# Payload_Power_Board.net
KiCad netlist of a schematic drawn in EAGLE
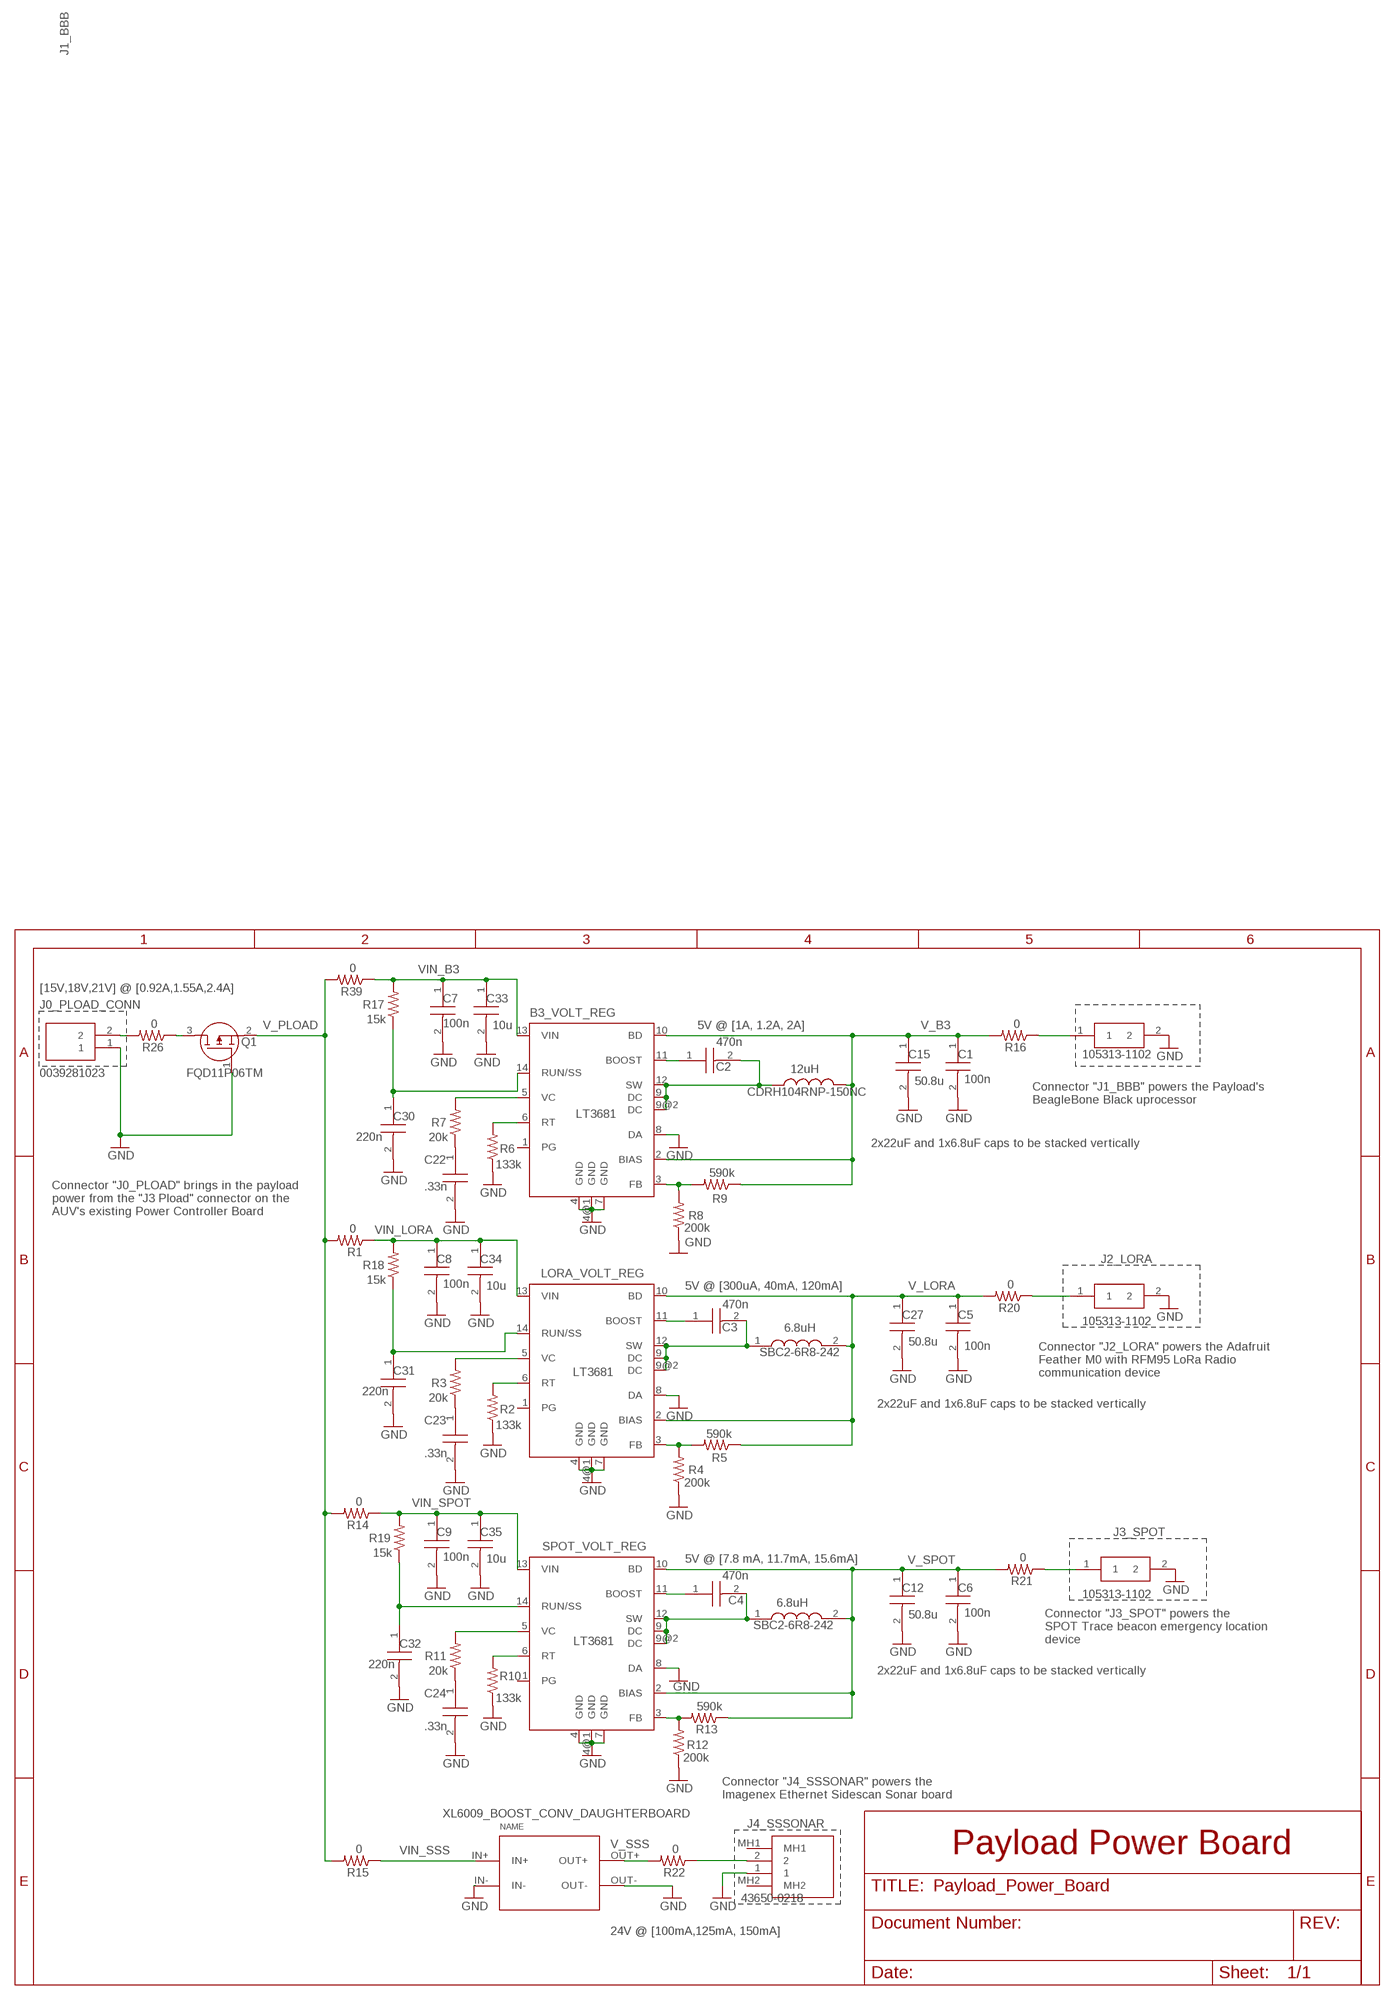
[diagram p0: schematic, sheet 1]

(export (version "E")
  (design (tool "Eeschema 10.0.6"))
  (components
    (comp (ref "B3_VOLT_REG")
      (value "LT3681")
      (footprint "eagle-import:DFN14-4X3DE")
      (fields (field (name "MPN") "LT3681EDE#PBF"))
      (libsource (lib "eagle-import") (part "LT3681"))
    )
    (comp (ref "C1")
      (value "100n")
      (footprint "eagle-import:CAPC1608X90N")
      (fields
        (field (name "MANUFACTURER_PART_NUMBER") "06033C104KAT4A")
        (field (name "MOUSER_PART_NUMBER") "581-06033C104KAT4A")
      )
      (libsource (lib "eagle-import") (part "06033C104KAT4A"))
    )
    (comp (ref "C2")
      (value "470n")
      (footprint "eagle-import:CAPC1608X90N")
      (fields
        (field (name "MANUFACTURER_PART_NUMBER") "06033C474JAT2A")
        (field (name "MOUSER_PART_NUMBER") "581-06033C474JAT2A")
      )
      (libsource (lib "eagle-import") (part "06033C474JAT2A"))
    )
    (comp (ref "C3")
      (value "470n")
      (footprint "eagle-import:CAPC1608X90N")
      (fields
        (field (name "MANUFACTURER_PART_NUMBER") "06033C474JAT2A")
        (field (name "MOUSER_PART_NUMBER") "581-06033C474JAT2A")
      )
      (libsource (lib "eagle-import") (part "06033C474JAT2A"))
    )
    (comp (ref "C4")
      (value "470n")
      (footprint "eagle-import:CAPC1608X90N")
      (fields
        (field (name "MANUFACTURER_PART_NUMBER") "06033C474JAT2A")
        (field (name "MOUSER_PART_NUMBER") "581-06033C474JAT2A")
      )
      (libsource (lib "eagle-import") (part "06033C474JAT2A"))
    )
    (comp (ref "C5")
      (value "100n")
      (footprint "eagle-import:CAPC1608X90N")
      (fields
        (field (name "MANUFACTURER_PART_NUMBER") "06033C104KAT4A")
        (field (name "MOUSER_PART_NUMBER") "581-06033C104KAT4A")
      )
      (libsource (lib "eagle-import") (part "06033C104KAT4A"))
    )
    (comp (ref "C6")
      (value "100n")
      (footprint "eagle-import:CAPC1608X90N")
      (fields
        (field (name "MANUFACTURER_PART_NUMBER") "06033C104KAT4A")
        (field (name "MOUSER_PART_NUMBER") "581-06033C104KAT4A")
      )
      (libsource (lib "eagle-import") (part "06033C104KAT4A"))
    )
    (comp (ref "C7")
      (value "100n")
      (footprint "eagle-import:CAPC1608X90N")
      (fields
        (field (name "MANUFACTURER_PART_NUMBER") "06031C104KAT2A")
        (field (name "MOUSER_PART_NUMBER") "581-06031C104KAT2A")
      )
      (libsource (lib "eagle-import") (part "06031C104KAT2A"))
    )
    (comp (ref "C8")
      (value "100n")
      (footprint "eagle-import:CAPC1608X90N")
      (fields
        (field (name "MANUFACTURER_PART_NUMBER") "06031C104KAT2A")
        (field (name "MOUSER_PART_NUMBER") "581-06031C104KAT2A")
      )
      (libsource (lib "eagle-import") (part "06031C104KAT2A"))
    )
    (comp (ref "C9")
      (value "100n")
      (footprint "eagle-import:CAPC1608X90N")
      (fields
        (field (name "MANUFACTURER_PART_NUMBER") "06031C104KAT2A")
        (field (name "MOUSER_PART_NUMBER") "581-06031C104KAT2A")
      )
      (libsource (lib "eagle-import") (part "06031C104KAT2A"))
    )
    (comp (ref "C12")
      (value "50.8u")
      (footprint "eagle-import:CAPC3225X279N")
      (fields
        (field (name "MANUFACTURER_PART_NUMBER") "12103C226KAT2A")
        (field (name "MOUSER_PART_NUMBER") "581-12103C226KAT2A")
      )
      (libsource (lib "eagle-import") (part "12103C226KAT2A"))
    )
    (comp (ref "C15")
      (value "50.8u")
      (footprint "eagle-import:CAPC3225X279N")
      (fields
        (field (name "MANUFACTURER_PART_NUMBER") "12103C226KAT2A")
        (field (name "MOUSER_PART_NUMBER") "581-12103C226KAT2A")
      )
      (libsource (lib "eagle-import") (part "12103C226KAT2A"))
    )
    (comp (ref "C22")
      (value ".33n")
      (footprint "eagle-import:CAPC2012X140N")
      (fields
        (field (name "MANUFACTURER_PART_NUMBER") "08053C334KAT2A")
        (field (name "MOUSER_PART_NUMBER") "581-08053C334KAT2A")
        (field (name "RS_PART_NUMBER") "1747387")
      )
      (libsource (lib "eagle-import") (part "08053C334KAT2A"))
    )
    (comp (ref "C23")
      (value ".33n")
      (footprint "eagle-import:CAPC2012X140N")
      (fields
        (field (name "MANUFACTURER_PART_NUMBER") "08053C334KAT2A")
        (field (name "MOUSER_PART_NUMBER") "581-08053C334KAT2A")
        (field (name "RS_PART_NUMBER") "1747387")
      )
      (libsource (lib "eagle-import") (part "08053C334KAT2A"))
    )
    (comp (ref "C24")
      (value ".33n")
      (footprint "eagle-import:CAPC2012X140N")
      (fields
        (field (name "MANUFACTURER_PART_NUMBER") "08053C334KAT2A")
        (field (name "MOUSER_PART_NUMBER") "581-08053C334KAT2A")
        (field (name "RS_PART_NUMBER") "1747387")
      )
      (libsource (lib "eagle-import") (part "08053C334KAT2A"))
    )
    (comp (ref "C27")
      (value "50.8u")
      (footprint "eagle-import:CAPC3225X279N")
      (fields
        (field (name "MANUFACTURER_PART_NUMBER") "12103C226KAT2A")
        (field (name "MOUSER_PART_NUMBER") "581-12103C226KAT2A")
      )
      (libsource (lib "eagle-import") (part "12103C226KAT2A"))
    )
    (comp (ref "C30")
      (value "220n")
      (footprint "eagle-import:CAPC2012X140N")
      (fields
        (field (name "MANUFACTURER_PART_NUMBER") "08051C224KAT2A")
        (field (name "MOUSER_PART_NUMBER") "581-08051C224KAT2A")
      )
      (libsource (lib "eagle-import") (part "08051C224KAT2A"))
    )
    (comp (ref "C31")
      (value "220n")
      (footprint "eagle-import:CAPC2012X140N")
      (fields
        (field (name "MANUFACTURER_PART_NUMBER") "08051C224KAT2A")
        (field (name "MOUSER_PART_NUMBER") "581-08051C224KAT2A")
      )
      (libsource (lib "eagle-import") (part "08051C224KAT2A"))
    )
    (comp (ref "C32")
      (value "220n")
      (footprint "eagle-import:CAPC2012X140N")
      (fields
        (field (name "MANUFACTURER_PART_NUMBER") "08051C224KAT2A")
        (field (name "MOUSER_PART_NUMBER") "581-08051C224KAT2A")
      )
      (libsource (lib "eagle-import") (part "08051C224KAT2A"))
    )
    (comp (ref "C33")
      (value "10u")
      (footprint "eagle-import:CAPC5750X279N")
      (fields
        (field (name "MANUFACTURER_PART_NUMBER") "22201C106KAT2A")
        (field (name "MOUSER_PART_NUMBER") "581-22201C106KAT2A")
      )
      (libsource (lib "eagle-import") (part "22201C106KAT2A"))
    )
    (comp (ref "C34")
      (value "10u")
      (footprint "eagle-import:CAPC5750X279N")
      (fields
        (field (name "MANUFACTURER_PART_NUMBER") "22201C106KAT2A")
        (field (name "MOUSER_PART_NUMBER") "581-22201C106KAT2A")
      )
      (libsource (lib "eagle-import") (part "22201C106KAT2A"))
    )
    (comp (ref "C35")
      (value "10u")
      (footprint "eagle-import:CAPC5750X279N")
      (fields
        (field (name "MANUFACTURER_PART_NUMBER") "22201C106KAT2A")
        (field (name "MOUSER_PART_NUMBER") "581-22201C106KAT2A")
      )
      (libsource (lib "eagle-import") (part "22201C106KAT2A"))
    )
    (comp (ref "INDUCTOR_3")
      (value "CDRH104RNP-150NC")
      (footprint "eagle-import:INDPM102100X400N")
      (fields (field (name "MOUSER_PART_NUMBER") "851-CDRH104RNP-150NC"))
      (libsource (lib "eagle-import") (part "CDRH104RNP-150NC"))
    )
    (comp (ref "J0_PLOAD_CONN")
      (value "0039281023")
      (footprint "eagle-import:SHDR2W145P0X550_1X2_960X540X13")
      (libsource (lib "eagle-import") (part "0039281023"))
    )
    (comp (ref "J1_BBB")
      (value "105313-1102")
      (footprint "eagle-import:1053131102")
      (fields (field (name "MOUSER_PART_NUMBER") "538-105313-1102") (field (name "RS_PART_NUMBER") "1623686"))
      (libsource (lib "eagle-import") (part "105313-1102"))
    )
    (comp (ref "J2_LORA")
      (value "105313-1102")
      (footprint "eagle-import:1053131102")
      (fields (field (name "MOUSER_PART_NUMBER") "538-105313-1102") (field (name "RS_PART_NUMBER") "1623686"))
      (libsource (lib "eagle-import") (part "105313-1102"))
    )
    (comp (ref "J3_SPOT")
      (value "105313-1102")
      (footprint "eagle-import:1053131102")
      (fields (field (name "MOUSER_PART_NUMBER") "538-105313-1102") (field (name "RS_PART_NUMBER") "1623686"))
      (libsource (lib "eagle-import") (part "105313-1102"))
    )
    (comp (ref "J4_SSSONAR")
      (value "43650-0218")
      (footprint "eagle-import:436500218")
      (fields (field (name "MOUSER_PART_NUMBER") "538-43650-0218") (field (name "RS_PART_NUMBER") "6704705P"))
      (libsource (lib "eagle-import") (part "43650-0218"))
    )
    (comp (ref "L4")
      (value "SBC2-6R8-242")
      (footprint "eagle-import:SBC26R8242")
      (fields (field (name "MOUSER_PART_NUMBER") "80-SBC2-6R8-242"))
      (libsource (lib "eagle-import") (part "SBC2-6R8-242"))
    )
    (comp (ref "L5")
      (value "SBC2-6R8-242")
      (footprint "eagle-import:SBC26R8242")
      (fields (field (name "MOUSER_PART_NUMBER") "80-SBC2-6R8-242"))
      (libsource (lib "eagle-import") (part "SBC2-6R8-242"))
    )
    (comp (ref "LORA_VOLT_REG")
      (value "LT3681")
      (footprint "eagle-import:DFN14-4X3DE")
      (fields (field (name "MPN") "LT3681EDE#PBF"))
      (libsource (lib "eagle-import") (part "LT3681"))
    )
    (comp (ref "Q1")
      (value "FQD11P06TM")
      (footprint "eagle-import:DPAK3-CASE-369AS")
      (fields (field (name "MOUSER_PART_NUMBER") "512-FQD11P06TM") (field (name "RS_PART_NUMBER") "6710949P"))
      (libsource (lib "eagle-import") (part "FQD11P06TM"))
    )
    (comp (ref "R1")
      (value "0")
      (footprint "eagle-import:0207_2V")
      (fields (field (name "MFR") "Yageo") (field (name "MPN") "RC0805FR-0710KL"))
      (libsource (lib "eagle-import") (part "R-US_0207/2V"))
    )
    (comp (ref "R2")
      (value "133k")
      (footprint "eagle-import:R0603")
      (libsource (lib "eagle-import") (part "R-US_R0603"))
    )
    (comp (ref "R3")
      (value "20k")
      (footprint "eagle-import:R0603")
      (libsource (lib "eagle-import") (part "R-US_R0603"))
    )
    (comp (ref "R4")
      (value "200k")
      (footprint "eagle-import:R0603")
      (libsource (lib "eagle-import") (part "R-US_R0603"))
    )
    (comp (ref "R5")
      (value "590k")
      (footprint "eagle-import:R0603")
      (libsource (lib "eagle-import") (part "R-US_R0603"))
    )
    (comp (ref "R6")
      (value "133k")
      (footprint "eagle-import:R0603")
      (libsource (lib "eagle-import") (part "R-US_R0603"))
    )
    (comp (ref "R7")
      (value "20k")
      (footprint "eagle-import:R0603")
      (libsource (lib "eagle-import") (part "R-US_R0603"))
    )
    (comp (ref "R8")
      (value "200k")
      (footprint "eagle-import:R0603")
      (libsource (lib "eagle-import") (part "R-US_R0603"))
    )
    (comp (ref "R9")
      (value "590k")
      (footprint "eagle-import:R0603")
      (libsource (lib "eagle-import") (part "R-US_R0603"))
    )
    (comp (ref "R10")
      (value "133k")
      (footprint "eagle-import:R0603")
      (libsource (lib "eagle-import") (part "R-US_R0603"))
    )
    (comp (ref "R11")
      (value "20k")
      (footprint "eagle-import:R0603")
      (libsource (lib "eagle-import") (part "R-US_R0603"))
    )
    (comp (ref "R12")
      (value "200k")
      (footprint "eagle-import:R0603")
      (libsource (lib "eagle-import") (part "R-US_R0603"))
    )
    (comp (ref "R13")
      (value "590k")
      (footprint "eagle-import:R0603")
      (libsource (lib "eagle-import") (part "R-US_R0603"))
    )
    (comp (ref "R14")
      (value "0")
      (footprint "eagle-import:0207_2V")
      (fields (field (name "MFR") "Yageo") (field (name "MPN") "RC0805FR-0710KL"))
      (libsource (lib "eagle-import") (part "R-US_0207/2V"))
    )
    (comp (ref "R15")
      (value "0")
      (footprint "eagle-import:0207_2V")
      (fields (field (name "MFR") "Yageo") (field (name "MPN") "RC0805FR-0710KL"))
      (libsource (lib "eagle-import") (part "R-US_0207/2V"))
    )
    (comp (ref "R16")
      (value "0")
      (footprint "eagle-import:0207_2V")
      (fields (field (name "MFR") "Yageo") (field (name "MPN") "RC0805FR-0710KL"))
      (libsource (lib "eagle-import") (part "R-US_0207/2V"))
    )
    (comp (ref "R17")
      (value "15k")
      (footprint "eagle-import:R0603")
      (libsource (lib "eagle-import") (part "R-US_R0603"))
    )
    (comp (ref "R18")
      (value "15k")
      (footprint "eagle-import:R0603")
      (libsource (lib "eagle-import") (part "R-US_R0603"))
    )
    (comp (ref "R19")
      (value "15k")
      (footprint "eagle-import:R0603")
      (libsource (lib "eagle-import") (part "R-US_R0603"))
    )
    (comp (ref "R20")
      (value "0")
      (footprint "eagle-import:0207_2V")
      (fields (field (name "MFR") "Yageo") (field (name "MPN") "RC0805FR-0710KL"))
      (libsource (lib "eagle-import") (part "R-US_0207/2V"))
    )
    (comp (ref "R21")
      (value "0")
      (footprint "eagle-import:0207_2V")
      (fields (field (name "MFR") "Yageo") (field (name "MPN") "RC0805FR-0710KL"))
      (libsource (lib "eagle-import") (part "R-US_0207/2V"))
    )
    (comp (ref "R22")
      (value "0")
      (footprint "eagle-import:0207_2V")
      (fields (field (name "MFR") "Yageo") (field (name "MPN") "RC0805FR-0710KL"))
      (libsource (lib "eagle-import") (part "R-US_0207/2V"))
    )
    (comp (ref "R26")
      (value "0")
      (footprint "eagle-import:0207_2V")
      (fields (field (name "MFR") "Yageo") (field (name "MPN") "RC0805FR-0710KL"))
      (libsource (lib "eagle-import") (part "R-US_0207/2V"))
    )
    (comp (ref "R39")
      (value "0")
      (footprint "eagle-import:0207_2V")
      (fields (field (name "MFR") "Yageo") (field (name "MPN") "RC0805FR-0710KL"))
      (libsource (lib "eagle-import") (part "R-US_0207/2V"))
    )
    (comp (ref "SPOT_VOLT_REG")
      (value "LT3681")
      (footprint "eagle-import:DFN14-4X3DE")
      (fields (field (name "MPN") "LT3681EDE#PBF"))
      (libsource (lib "eagle-import") (part "LT3681"))
    )
    (comp (ref "XL6009_BOOST_CONV_DAUGHTERBOARD")
      (value "XL6009")
      (footprint "eagle-import:CP8-ADJ")
      (libsource (lib "eagle-import") (part "CP8-ADJ"))
    )
  )
  (nets
    (net (code "1") (name "/VIN_B3") (class "Default")
      (node (ref "B3_VOLT_REG") (pin "13") (pinfunction "VIN_13") (pintype "input"))
      (node (ref "C33") (pin "1") (pinfunction "1_1") (pintype "bidirectional"))
      (node (ref "C7") (pin "1") (pinfunction "1_1") (pintype "bidirectional"))
      (node (ref "R17") (pin "2") (pinfunction "2_2") (pintype "passive"))
      (node (ref "R39") (pin "1") (pinfunction "1_1") (pintype "passive"))
    )
    (net (code "2") (name "/VIN_LORA") (class "Default")
      (node (ref "C34") (pin "1") (pinfunction "1_1") (pintype "bidirectional"))
      (node (ref "C8") (pin "1") (pinfunction "1_1") (pintype "bidirectional"))
      (node (ref "LORA_VOLT_REG") (pin "13") (pinfunction "VIN_13") (pintype "input"))
      (node (ref "R1") (pin "1") (pinfunction "1_1") (pintype "passive"))
      (node (ref "R18") (pin "2") (pinfunction "2_2") (pintype "passive"))
    )
    (net (code "3") (name "/VIN_SPOT") (class "Default")
      (node (ref "C35") (pin "1") (pinfunction "1_1") (pintype "bidirectional"))
      (node (ref "C9") (pin "1") (pinfunction "1_1") (pintype "bidirectional"))
      (node (ref "R14") (pin "1") (pinfunction "1_1") (pintype "passive"))
      (node (ref "R19") (pin "2") (pinfunction "2_2") (pintype "passive"))
      (node (ref "SPOT_VOLT_REG") (pin "13") (pinfunction "VIN_13") (pintype "input"))
    )
    (net (code "4") (name "/VIN_SSS") (class "Default")
      (node (ref "R15") (pin "1") (pinfunction "1_1") (pintype "passive"))
      (node (ref "XL6009_BOOST_CONV_DAUGHTERBOARD") (pin "IN+") (pinfunction "IN+_IN+") (pintype "passive"))
    )
    (net (code "5") (name "/V_B3") (class "Default")
      (node (ref "B3_VOLT_REG") (pin "10") (pinfunction "BD_10") (pintype "input"))
      (node (ref "B3_VOLT_REG") (pin "2") (pinfunction "BIAS_2") (pintype "input"))
      (node (ref "C1") (pin "1") (pinfunction "1_1") (pintype "bidirectional"))
      (node (ref "C15") (pin "1") (pinfunction "1_1") (pintype "bidirectional"))
      (node (ref "INDUCTOR_3") (pin "2") (pinfunction "2_2") (pintype "passive"))
      (node (ref "R16") (pin "2") (pinfunction "2_2") (pintype "passive"))
      (node (ref "R9") (pin "1") (pinfunction "1_1") (pintype "passive"))
    )
    (net (code "6") (name "/V_LORA") (class "Default")
      (node (ref "C27") (pin "1") (pinfunction "1_1") (pintype "bidirectional"))
      (node (ref "C5") (pin "1") (pinfunction "1_1") (pintype "bidirectional"))
      (node (ref "L5") (pin "2") (pinfunction "2_2") (pintype "bidirectional"))
      (node (ref "LORA_VOLT_REG") (pin "10") (pinfunction "BD_10") (pintype "input"))
      (node (ref "LORA_VOLT_REG") (pin "2") (pinfunction "BIAS_2") (pintype "input"))
      (node (ref "R20") (pin "2") (pinfunction "2_2") (pintype "passive"))
      (node (ref "R5") (pin "1") (pinfunction "1_1") (pintype "passive"))
    )
    (net (code "7") (name "/V_PLOAD") (class "Default")
      (node (ref "Q1") (pin "2") (pinfunction "S_2") (pintype "bidirectional"))
      (node (ref "R1") (pin "2") (pinfunction "2_2") (pintype "passive"))
      (node (ref "R14") (pin "2") (pinfunction "2_2") (pintype "passive"))
      (node (ref "R15") (pin "2") (pinfunction "2_2") (pintype "passive"))
      (node (ref "R39") (pin "2") (pinfunction "2_2") (pintype "passive"))
    )
    (net (code "8") (name "/V_SPOT") (class "Default")
      (node (ref "C12") (pin "1") (pinfunction "1_1") (pintype "bidirectional"))
      (node (ref "C6") (pin "1") (pinfunction "1_1") (pintype "bidirectional"))
      (node (ref "L4") (pin "2") (pinfunction "2_2") (pintype "bidirectional"))
      (node (ref "R13") (pin "1") (pinfunction "1_1") (pintype "passive"))
      (node (ref "R21") (pin "2") (pinfunction "2_2") (pintype "passive"))
      (node (ref "SPOT_VOLT_REG") (pin "10") (pinfunction "BD_10") (pintype "input"))
      (node (ref "SPOT_VOLT_REG") (pin "2") (pinfunction "BIAS_2") (pintype "input"))
    )
    (net (code "9") (name "/V_SSS") (class "Default")
      (node (ref "R22") (pin "2") (pinfunction "2_2") (pintype "passive"))
      (node (ref "XL6009_BOOST_CONV_DAUGHTERBOARD") (pin "OUT+") (pinfunction "OUT+_OUT+") (pintype "passive"))
    )
    (net (code "10") (name "GND") (class "Default")
      (node (ref "B3_VOLT_REG") (pin "4") (pinfunction "GND_4") (pintype "input"))
      (node (ref "B3_VOLT_REG") (pin "4@1") (pinfunction "GND_4@1") (pintype "input"))
      (node (ref "B3_VOLT_REG") (pin "7") (pinfunction "GND_7") (pintype "input"))
      (node (ref "B3_VOLT_REG") (pin "8") (pinfunction "DA_8") (pintype "passive"))
      (node (ref "C1") (pin "2") (pinfunction "2_2") (pintype "bidirectional"))
      (node (ref "C12") (pin "2") (pinfunction "2_2") (pintype "bidirectional"))
      (node (ref "C15") (pin "2") (pinfunction "2_2") (pintype "bidirectional"))
      (node (ref "C22") (pin "2") (pinfunction "2_2") (pintype "bidirectional"))
      (node (ref "C23") (pin "2") (pinfunction "2_2") (pintype "bidirectional"))
      (node (ref "C24") (pin "2") (pinfunction "2_2") (pintype "bidirectional"))
      (node (ref "C27") (pin "2") (pinfunction "2_2") (pintype "bidirectional"))
      (node (ref "C30") (pin "2") (pinfunction "2_2") (pintype "bidirectional"))
      (node (ref "C31") (pin "2") (pinfunction "2_2") (pintype "bidirectional"))
      (node (ref "C32") (pin "2") (pinfunction "2_2") (pintype "bidirectional"))
      (node (ref "C33") (pin "2") (pinfunction "2_2") (pintype "bidirectional"))
      (node (ref "C34") (pin "2") (pinfunction "2_2") (pintype "bidirectional"))
      (node (ref "C35") (pin "2") (pinfunction "2_2") (pintype "bidirectional"))
      (node (ref "C5") (pin "2") (pinfunction "2_2") (pintype "bidirectional"))
      (node (ref "C6") (pin "2") (pinfunction "2_2") (pintype "bidirectional"))
      (node (ref "C7") (pin "2") (pinfunction "2_2") (pintype "bidirectional"))
      (node (ref "C8") (pin "2") (pinfunction "2_2") (pintype "bidirectional"))
      (node (ref "C9") (pin "2") (pinfunction "2_2") (pintype "bidirectional"))
      (node (ref "J0_PLOAD_CONN") (pin "1") (pinfunction "1_1") (pintype "bidirectional"))
      (node (ref "J1_BBB") (pin "2") (pinfunction "2_2") (pintype "bidirectional"))
      (node (ref "J2_LORA") (pin "2") (pinfunction "2_2") (pintype "bidirectional"))
      (node (ref "J3_SPOT") (pin "2") (pinfunction "2_2") (pintype "bidirectional"))
      (node (ref "J4_SSSONAR") (pin "1") (pinfunction "1_1") (pintype "bidirectional"))
      (node (ref "LORA_VOLT_REG") (pin "4") (pinfunction "GND_4") (pintype "input"))
      (node (ref "LORA_VOLT_REG") (pin "4@1") (pinfunction "GND_4@1") (pintype "input"))
      (node (ref "LORA_VOLT_REG") (pin "7") (pinfunction "GND_7") (pintype "input"))
      (node (ref "LORA_VOLT_REG") (pin "8") (pinfunction "DA_8") (pintype "passive"))
      (node (ref "Q1") (pin "1") (pinfunction "G_1") (pintype "bidirectional"))
      (node (ref "R10") (pin "1") (pinfunction "1_1") (pintype "passive"))
      (node (ref "R12") (pin "1") (pinfunction "1_1") (pintype "passive"))
      (node (ref "R2") (pin "1") (pinfunction "1_1") (pintype "passive"))
      (node (ref "R4") (pin "1") (pinfunction "1_1") (pintype "passive"))
      (node (ref "R6") (pin "1") (pinfunction "1_1") (pintype "passive"))
      (node (ref "R8") (pin "1") (pinfunction "1_1") (pintype "passive"))
      (node (ref "SPOT_VOLT_REG") (pin "4") (pinfunction "GND_4") (pintype "input"))
      (node (ref "SPOT_VOLT_REG") (pin "4@1") (pinfunction "GND_4@1") (pintype "input"))
      (node (ref "SPOT_VOLT_REG") (pin "7") (pinfunction "GND_7") (pintype "input"))
      (node (ref "SPOT_VOLT_REG") (pin "8") (pinfunction "DA_8") (pintype "passive"))
      (node (ref "XL6009_BOOST_CONV_DAUGHTERBOARD") (pin "IN-") (pinfunction "IN-_IN-") (pintype "passive"))
      (node (ref "XL6009_BOOST_CONV_DAUGHTERBOARD") (pin "OUT-") (pinfunction "OUT-_OUT-") (pintype "passive"))
    )
    (net (code "11") (name "Net-(B3_VOLT_REG-BOOST)") (class "Default")
      (node (ref "B3_VOLT_REG") (pin "11") (pinfunction "BOOST_11") (pintype "output"))
      (node (ref "C2") (pin "1") (pinfunction "1_1") (pintype "bidirectional"))
    )
    (net (code "12") (name "Net-(B3_VOLT_REG-FB)") (class "Default")
      (node (ref "B3_VOLT_REG") (pin "3") (pinfunction "FB_3") (pintype "input"))
      (node (ref "R8") (pin "2") (pinfunction "2_2") (pintype "passive"))
      (node (ref "R9") (pin "2") (pinfunction "2_2") (pintype "passive"))
    )
    (net (code "13") (name "Net-(B3_VOLT_REG-RT)") (class "Default")
      (node (ref "B3_VOLT_REG") (pin "6") (pinfunction "RT_6") (pintype "input"))
      (node (ref "R6") (pin "2") (pinfunction "2_2") (pintype "passive"))
    )
    (net (code "14") (name "Net-(B3_VOLT_REG-RUN{slash}SS)") (class "Default")
      (node (ref "B3_VOLT_REG") (pin "14") (pinfunction "RUN/SS_14") (pintype "input"))
      (node (ref "C30") (pin "1") (pinfunction "1_1") (pintype "bidirectional"))
      (node (ref "R17") (pin "1") (pinfunction "1_1") (pintype "passive"))
    )
    (net (code "15") (name "Net-(B3_VOLT_REG-SW)") (class "Default")
      (node (ref "B3_VOLT_REG") (pin "12") (pinfunction "SW_12") (pintype "output"))
      (node (ref "B3_VOLT_REG") (pin "9") (pinfunction "DC_9") (pintype "passive"))
      (node (ref "B3_VOLT_REG") (pin "9@2") (pinfunction "DC_9@2") (pintype "passive"))
      (node (ref "C2") (pin "2") (pinfunction "2_2") (pintype "bidirectional"))
      (node (ref "INDUCTOR_3") (pin "1") (pinfunction "1_1") (pintype "passive"))
    )
    (net (code "16") (name "Net-(B3_VOLT_REG-VC)") (class "Default")
      (node (ref "B3_VOLT_REG") (pin "5") (pinfunction "VC_5") (pintype "output"))
      (node (ref "R7") (pin "2") (pinfunction "2_2") (pintype "passive"))
    )
    (net (code "17") (name "Net-(C22-Pad1)") (class "Default")
      (node (ref "C22") (pin "1") (pinfunction "1_1") (pintype "bidirectional"))
      (node (ref "R7") (pin "1") (pinfunction "1_1") (pintype "passive"))
    )
    (net (code "18") (name "Net-(C23-Pad1)") (class "Default")
      (node (ref "C23") (pin "1") (pinfunction "1_1") (pintype "bidirectional"))
      (node (ref "R3") (pin "1") (pinfunction "1_1") (pintype "passive"))
    )
    (net (code "19") (name "Net-(C24-Pad1)") (class "Default")
      (node (ref "C24") (pin "1") (pinfunction "1_1") (pintype "bidirectional"))
      (node (ref "R11") (pin "1") (pinfunction "1_1") (pintype "passive"))
    )
    (net (code "20") (name "Net-(J0_PLOAD_CONN-Pad2)") (class "Default")
      (node (ref "J0_PLOAD_CONN") (pin "2") (pinfunction "2_2") (pintype "bidirectional"))
      (node (ref "R26") (pin "2") (pinfunction "2_2") (pintype "passive"))
    )
    (net (code "21") (name "Net-(J1_BBB-Pad1)") (class "Default")
      (node (ref "J1_BBB") (pin "1") (pinfunction "1_1") (pintype "bidirectional"))
      (node (ref "R16") (pin "1") (pinfunction "1_1") (pintype "passive"))
    )
    (net (code "22") (name "Net-(J2_LORA-Pad1)") (class "Default")
      (node (ref "J2_LORA") (pin "1") (pinfunction "1_1") (pintype "bidirectional"))
      (node (ref "R20") (pin "1") (pinfunction "1_1") (pintype "passive"))
    )
    (net (code "23") (name "Net-(J3_SPOT-Pad1)") (class "Default")
      (node (ref "J3_SPOT") (pin "1") (pinfunction "1_1") (pintype "bidirectional"))
      (node (ref "R21") (pin "1") (pinfunction "1_1") (pintype "passive"))
    )
    (net (code "24") (name "Net-(J4_SSSONAR-Pad2)") (class "Default")
      (node (ref "J4_SSSONAR") (pin "2") (pinfunction "2_2") (pintype "bidirectional"))
      (node (ref "R22") (pin "1") (pinfunction "1_1") (pintype "passive"))
    )
    (net (code "25") (name "Net-(LORA_VOLT_REG-BOOST)") (class "Default")
      (node (ref "C3") (pin "1") (pinfunction "1_1") (pintype "bidirectional"))
      (node (ref "LORA_VOLT_REG") (pin "11") (pinfunction "BOOST_11") (pintype "output"))
    )
    (net (code "26") (name "Net-(LORA_VOLT_REG-FB)") (class "Default")
      (node (ref "LORA_VOLT_REG") (pin "3") (pinfunction "FB_3") (pintype "input"))
      (node (ref "R4") (pin "2") (pinfunction "2_2") (pintype "passive"))
      (node (ref "R5") (pin "2") (pinfunction "2_2") (pintype "passive"))
    )
    (net (code "27") (name "Net-(LORA_VOLT_REG-RT)") (class "Default")
      (node (ref "LORA_VOLT_REG") (pin "6") (pinfunction "RT_6") (pintype "input"))
      (node (ref "R2") (pin "2") (pinfunction "2_2") (pintype "passive"))
    )
    (net (code "28") (name "Net-(LORA_VOLT_REG-RUN{slash}SS)") (class "Default")
      (node (ref "C31") (pin "1") (pinfunction "1_1") (pintype "bidirectional"))
      (node (ref "LORA_VOLT_REG") (pin "14") (pinfunction "RUN/SS_14") (pintype "input"))
      (node (ref "R18") (pin "1") (pinfunction "1_1") (pintype "passive"))
    )
    (net (code "29") (name "Net-(LORA_VOLT_REG-SW)") (class "Default")
      (node (ref "C3") (pin "2") (pinfunction "2_2") (pintype "bidirectional"))
      (node (ref "L5") (pin "1") (pinfunction "1_1") (pintype "bidirectional"))
      (node (ref "LORA_VOLT_REG") (pin "12") (pinfunction "SW_12") (pintype "output"))
      (node (ref "LORA_VOLT_REG") (pin "9") (pinfunction "DC_9") (pintype "passive"))
      (node (ref "LORA_VOLT_REG") (pin "9@2") (pinfunction "DC_9@2") (pintype "passive"))
    )
    (net (code "30") (name "Net-(LORA_VOLT_REG-VC)") (class "Default")
      (node (ref "LORA_VOLT_REG") (pin "5") (pinfunction "VC_5") (pintype "output"))
      (node (ref "R3") (pin "2") (pinfunction "2_2") (pintype "passive"))
    )
    (net (code "31") (name "Net-(Q1-D)") (class "Default")
      (node (ref "Q1") (pin "3") (pinfunction "D_3") (pintype "bidirectional"))
      (node (ref "R26") (pin "1") (pinfunction "1_1") (pintype "passive"))
    )
    (net (code "32") (name "Net-(SPOT_VOLT_REG-BOOST)") (class "Default")
      (node (ref "C4") (pin "1") (pinfunction "1_1") (pintype "bidirectional"))
      (node (ref "SPOT_VOLT_REG") (pin "11") (pinfunction "BOOST_11") (pintype "output"))
    )
    (net (code "33") (name "Net-(SPOT_VOLT_REG-FB)") (class "Default")
      (node (ref "R12") (pin "2") (pinfunction "2_2") (pintype "passive"))
      (node (ref "R13") (pin "2") (pinfunction "2_2") (pintype "passive"))
      (node (ref "SPOT_VOLT_REG") (pin "3") (pinfunction "FB_3") (pintype "input"))
    )
    (net (code "34") (name "Net-(SPOT_VOLT_REG-RT)") (class "Default")
      (node (ref "R10") (pin "2") (pinfunction "2_2") (pintype "passive"))
      (node (ref "SPOT_VOLT_REG") (pin "6") (pinfunction "RT_6") (pintype "input"))
    )
    (net (code "35") (name "Net-(SPOT_VOLT_REG-RUN{slash}SS)") (class "Default")
      (node (ref "C32") (pin "1") (pinfunction "1_1") (pintype "bidirectional"))
      (node (ref "R19") (pin "1") (pinfunction "1_1") (pintype "passive"))
      (node (ref "SPOT_VOLT_REG") (pin "14") (pinfunction "RUN/SS_14") (pintype "input"))
    )
    (net (code "36") (name "Net-(SPOT_VOLT_REG-SW)") (class "Default")
      (node (ref "C4") (pin "2") (pinfunction "2_2") (pintype "bidirectional"))
      (node (ref "L4") (pin "1") (pinfunction "1_1") (pintype "bidirectional"))
      (node (ref "SPOT_VOLT_REG") (pin "12") (pinfunction "SW_12") (pintype "output"))
      (node (ref "SPOT_VOLT_REG") (pin "9") (pinfunction "DC_9") (pintype "passive"))
      (node (ref "SPOT_VOLT_REG") (pin "9@2") (pinfunction "DC_9@2") (pintype "passive"))
    )
    (net (code "37") (name "Net-(SPOT_VOLT_REG-VC)") (class "Default")
      (node (ref "R11") (pin "2") (pinfunction "2_2") (pintype "passive"))
      (node (ref "SPOT_VOLT_REG") (pin "5") (pinfunction "VC_5") (pintype "output"))
    )
    (net (code "38") (name "unconnected-(B3_VOLT_REG-PG-Pad1)") (class "Default")
      (node (ref "B3_VOLT_REG") (pin "1") (pinfunction "PG_1") (pintype "open_collector"))
    )
    (net (code "39") (name "unconnected-(J4_SSSONAR-PadMH1)") (class "Default")
      (node (ref "J4_SSSONAR") (pin "MH1") (pinfunction "MH1_MH1") (pintype "bidirectional"))
    )
    (net (code "40") (name "unconnected-(J4_SSSONAR-PadMH2)") (class "Default")
      (node (ref "J4_SSSONAR") (pin "MH2") (pinfunction "MH2_MH2") (pintype "bidirectional"))
    )
    (net (code "41") (name "unconnected-(LORA_VOLT_REG-PG-Pad1)") (class "Default")
      (node (ref "LORA_VOLT_REG") (pin "1") (pinfunction "PG_1") (pintype "open_collector"))
    )
    (net (code "42") (name "unconnected-(SPOT_VOLT_REG-PG-Pad1)") (class "Default")
      (node (ref "SPOT_VOLT_REG") (pin "1") (pinfunction "PG_1") (pintype "open_collector"))
    )
  )
)
